# Oscillator.net
KiCad netlist of a schematic drawn in EAGLE
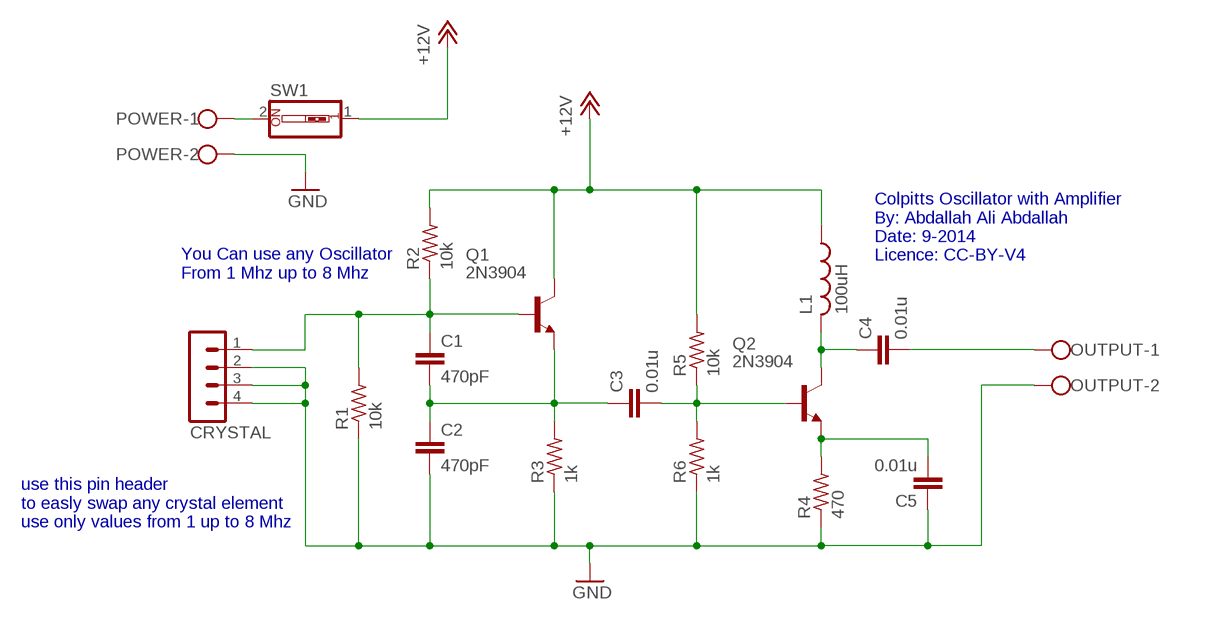
[diagram p0: schematic, sheet 1]

(export (version "E")
  (design (tool "Eeschema 10.0.6"))
  (components
    (comp (ref "C1")
      (value "470pF")
      (footprint "eagle-import:C025-025X050")
      (libsource (lib "eagle-import") (part "C-EU025-025X050"))
    )
    (comp (ref "C2")
      (value "470pF")
      (footprint "eagle-import:C025-025X050")
      (libsource (lib "eagle-import") (part "C-EU025-025X050"))
    )
    (comp (ref "C3")
      (value "0.01u")
      (footprint "eagle-import:C025-025X050")
      (libsource (lib "eagle-import") (part "C-EU025-025X050"))
    )
    (comp (ref "C4")
      (value "0.01u")
      (footprint "eagle-import:C025-025X050")
      (libsource (lib "eagle-import") (part "C-EU025-025X050"))
    )
    (comp (ref "C5")
      (value "0.01u")
      (footprint "eagle-import:C025-025X050")
      (libsource (lib "eagle-import") (part "C-EU025-025X050"))
    )
    (comp (ref "CRYSTAL")
      (value "MA04-1")
      (footprint "eagle-import:MA04-1")
      (libsource (lib "eagle-import") (part "MA04-1"))
    )
    (comp (ref "L1")
      (value "100uH")
      (footprint "eagle-import:0204_7")
      (libsource (lib "eagle-import") (part "L-US0204/7"))
    )
    (comp (ref "OUTPUT")
      (value "W237-102")
      (footprint "eagle-import:W237-102")
      (fields (field (name "MPN") "237-102"))
      (libsource (lib "eagle-import") (part "W237-102"))
    )
    (comp (ref "POWER")
      (value "W237-102")
      (footprint "eagle-import:W237-102")
      (fields (field (name "MPN") "237-102"))
      (libsource (lib "eagle-import") (part "W237-102"))
    )
    (comp (ref "Q1")
      (value "2N3904")
      (footprint "eagle-import:TO92")
      (libsource (lib "eagle-import") (part "2N3904"))
    )
    (comp (ref "Q2")
      (value "2N3904")
      (footprint "eagle-import:TO92")
      (libsource (lib "eagle-import") (part "2N3904"))
    )
    (comp (ref "R1")
      (value "10k")
      (footprint "eagle-import:0204_7")
      (libsource (lib "eagle-import") (part "R-US_0204/7"))
    )
    (comp (ref "R2")
      (value "10k")
      (footprint "eagle-import:0204_7")
      (libsource (lib "eagle-import") (part "R-US_0204/7"))
    )
    (comp (ref "R3")
      (value "1k")
      (footprint "eagle-import:0204_7")
      (libsource (lib "eagle-import") (part "R-US_0204/7"))
    )
    (comp (ref "R4")
      (value "470")
      (footprint "eagle-import:0204_7")
      (libsource (lib "eagle-import") (part "R-US_0204/7"))
    )
    (comp (ref "R5")
      (value "10k")
      (footprint "eagle-import:0204_7")
      (libsource (lib "eagle-import") (part "R-US_0204/7"))
    )
    (comp (ref "R6")
      (value "1k")
      (footprint "eagle-import:0204_7")
      (libsource (lib "eagle-import") (part "R-US_0204/7"))
    )
    (comp (ref "SW1")
      (value "SW_DIP-1")
      (footprint "eagle-import:EDG-01")
      (libsource (lib "eagle-import") (part "SW_DIP-1"))
    )
  )
  (nets
    (net (code "1") (name "+12V") (class "Default")
      (node (ref "L1") (pin "1") (pinfunction "1_1") (pintype "passive"))
      (node (ref "Q1") (pin "1") (pinfunction "C_1") (pintype "passive"))
      (node (ref "R2") (pin "2") (pinfunction "2_2") (pintype "passive"))
      (node (ref "R5") (pin "2") (pinfunction "2_2") (pintype "passive"))
      (node (ref "SW1") (pin "1") (pinfunction "1_1") (pintype "passive"))
    )
    (net (code "2") (name "GND") (class "Default")
      (node (ref "C2") (pin "2") (pinfunction "2_2") (pintype "passive"))
      (node (ref "C5") (pin "1") (pinfunction "1_1") (pintype "passive"))
      (node (ref "CRYSTAL") (pin "2") (pinfunction "2_2") (pintype "passive"))
      (node (ref "CRYSTAL") (pin "3") (pinfunction "3_3") (pintype "passive"))
      (node (ref "CRYSTAL") (pin "4") (pinfunction "4_4") (pintype "passive"))
      (node (ref "OUTPUT") (pin "2") (pinfunction "KL_2") (pintype "passive"))
      (node (ref "POWER") (pin "2") (pinfunction "KL_2") (pintype "passive"))
      (node (ref "R1") (pin "1") (pinfunction "1_1") (pintype "passive"))
      (node (ref "R3") (pin "1") (pinfunction "1_1") (pintype "passive"))
      (node (ref "R4") (pin "1") (pinfunction "1_1") (pintype "passive"))
      (node (ref "R6") (pin "1") (pinfunction "1_1") (pintype "passive"))
    )
    (net (code "3") (name "Net-(OUTPUTA-KL)") (class "Default")
      (node (ref "C4") (pin "2") (pinfunction "2_2") (pintype "passive"))
      (node (ref "OUTPUT") (pin "1") (pinfunction "KL_1") (pintype "passive"))
    )
    (net (code "4") (name "Net-(POWERA-KL)") (class "Default")
      (node (ref "POWER") (pin "1") (pinfunction "KL_1") (pintype "passive"))
      (node (ref "SW1") (pin "2") (pinfunction "2_2") (pintype "passive"))
    )
    (net (code "5") (name "Net-(Q1-B)") (class "Default")
      (node (ref "C1") (pin "1") (pinfunction "1_1") (pintype "passive"))
      (node (ref "CRYSTAL") (pin "1") (pinfunction "1_1") (pintype "passive"))
      (node (ref "Q1") (pin "2") (pinfunction "B_2") (pintype "passive"))
      (node (ref "R1") (pin "2") (pinfunction "2_2") (pintype "passive"))
      (node (ref "R2") (pin "1") (pinfunction "1_1") (pintype "passive"))
    )
    (net (code "6") (name "Net-(Q1-E)") (class "Default")
      (node (ref "C1") (pin "2") (pinfunction "2_2") (pintype "passive"))
      (node (ref "C2") (pin "1") (pinfunction "1_1") (pintype "passive"))
      (node (ref "C3") (pin "1") (pinfunction "1_1") (pintype "passive"))
      (node (ref "Q1") (pin "3") (pinfunction "E_3") (pintype "passive"))
      (node (ref "R3") (pin "2") (pinfunction "2_2") (pintype "passive"))
    )
    (net (code "7") (name "Net-(Q2-B)") (class "Default")
      (node (ref "C3") (pin "2") (pinfunction "2_2") (pintype "passive"))
      (node (ref "Q2") (pin "2") (pinfunction "B_2") (pintype "passive"))
      (node (ref "R5") (pin "1") (pinfunction "1_1") (pintype "passive"))
      (node (ref "R6") (pin "2") (pinfunction "2_2") (pintype "passive"))
    )
    (net (code "8") (name "Net-(Q2-C)") (class "Default")
      (node (ref "C4") (pin "1") (pinfunction "1_1") (pintype "passive"))
      (node (ref "L1") (pin "2") (pinfunction "2_2") (pintype "passive"))
      (node (ref "Q2") (pin "1") (pinfunction "C_1") (pintype "passive"))
    )
    (net (code "9") (name "Net-(Q2-E)") (class "Default")
      (node (ref "C5") (pin "2") (pinfunction "2_2") (pintype "passive"))
      (node (ref "Q2") (pin "3") (pinfunction "E_3") (pintype "passive"))
      (node (ref "R4") (pin "2") (pinfunction "2_2") (pintype "passive"))
    )
  )
)
